# numpad.net
KiCad netlist of a schematic drawn in EAGLE
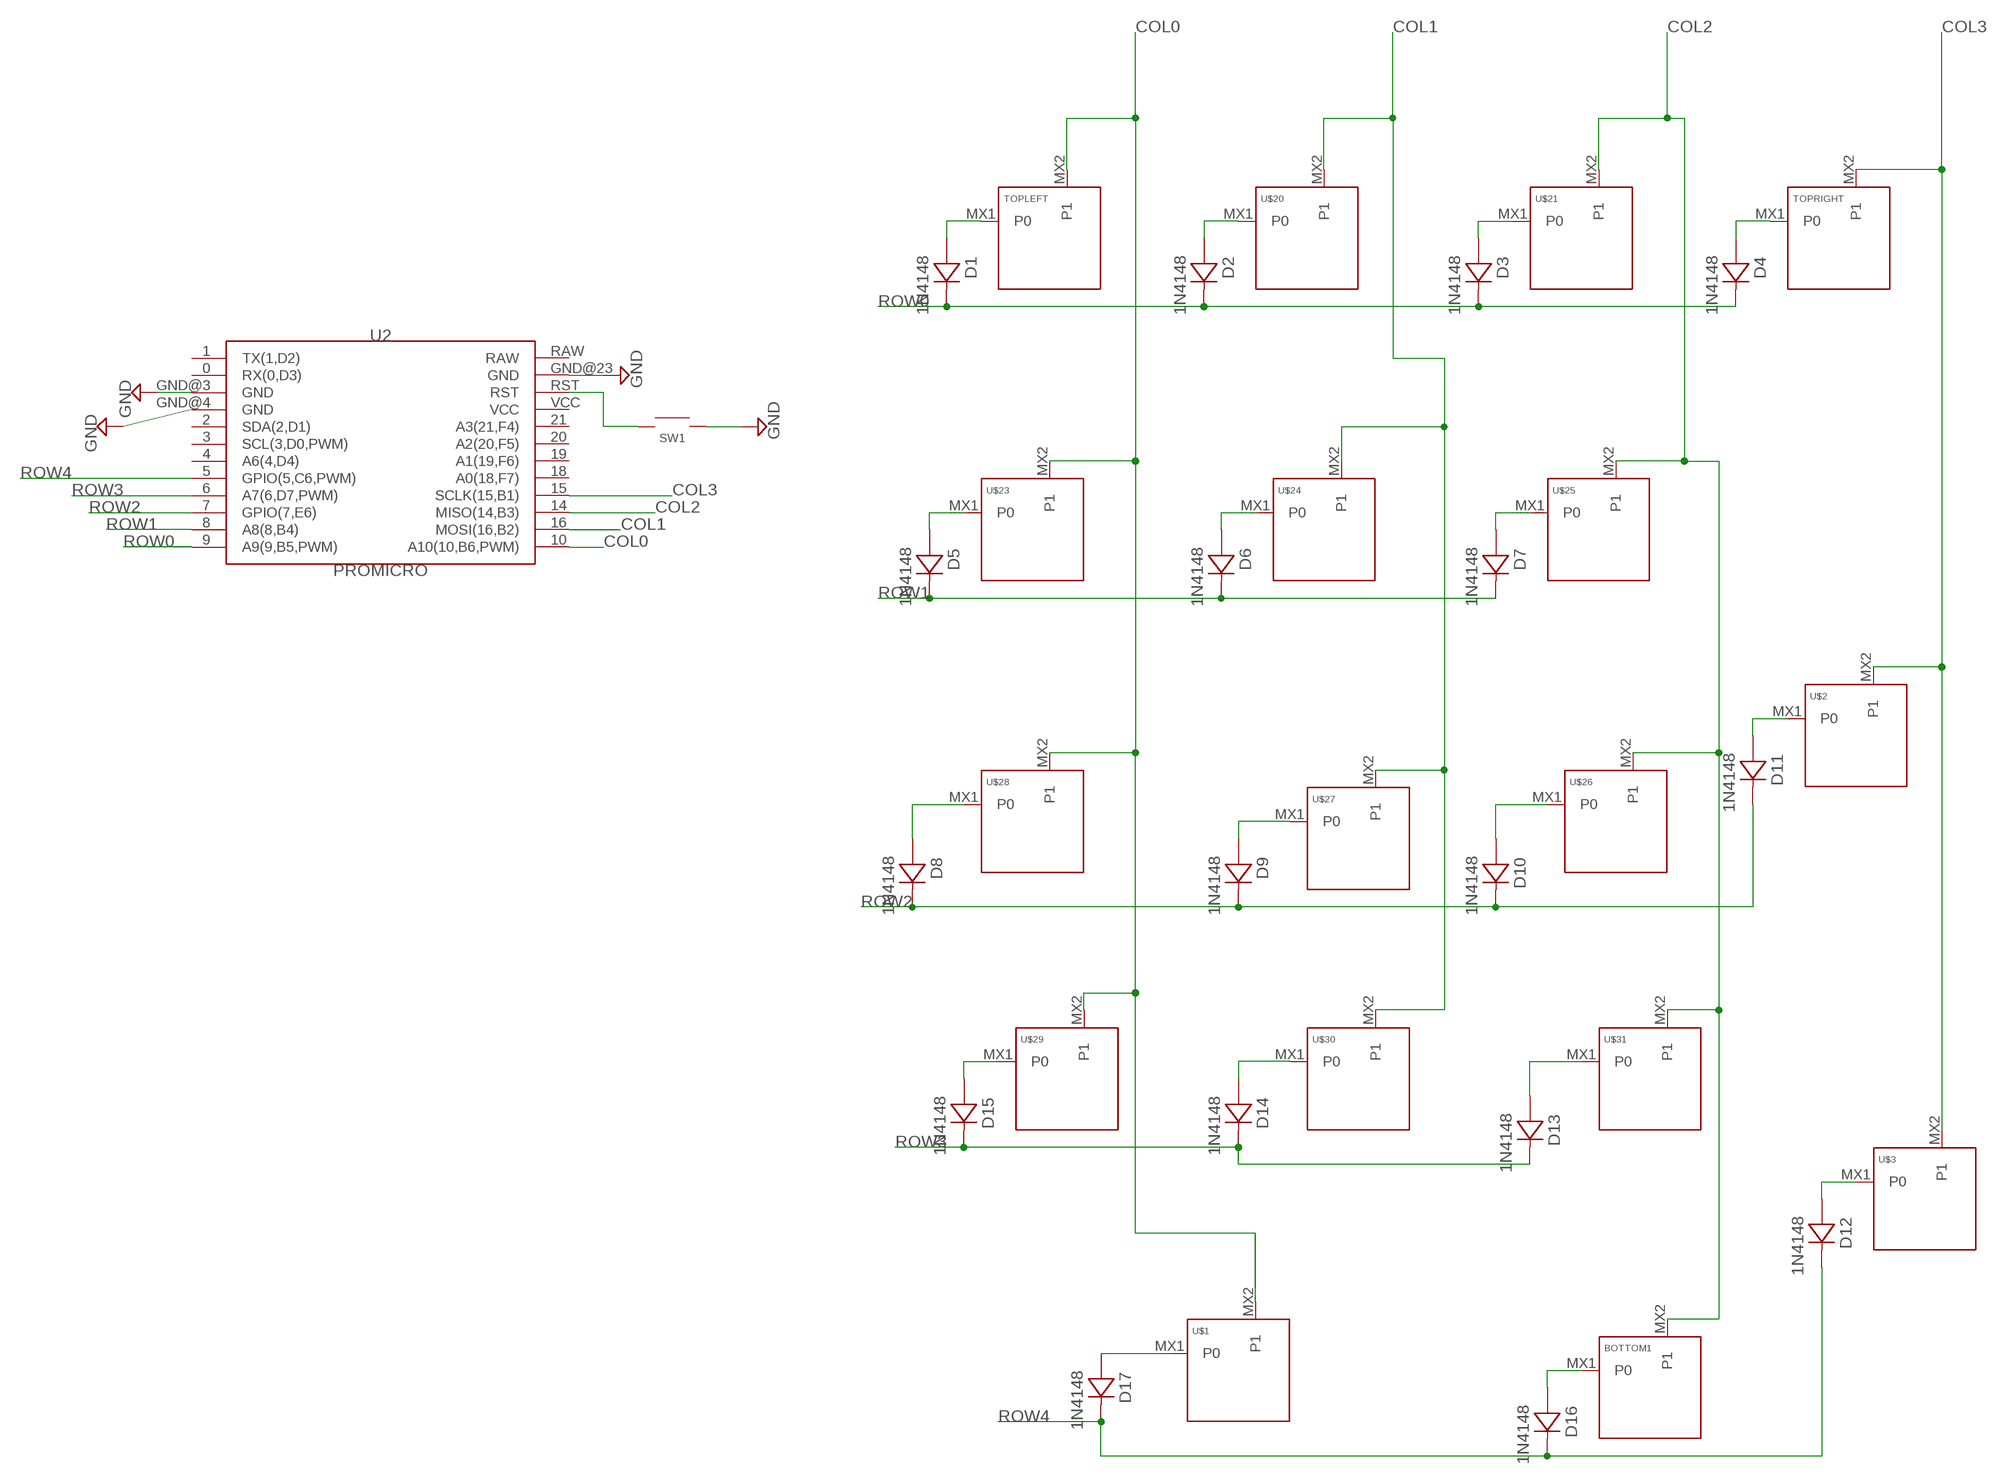
[diagram p0: schematic, sheet 1]

(export (version "E")
  (design (tool "Eeschema 10.0.6"))
  (components
    (comp (ref "BOTTOM1")
      (value "KEYSWITCH-PLAIN-MX-1U")
      (footprint "eagle-import:MX-1U")
      (libsource (lib "eagle-import") (part "KEYSWITCH-PLAIN-MX-1U"))
    )
    (comp (ref "D1")
      (value "1N4148")
      (footprint "eagle-import:DO-35")
      (libsource (lib "eagle-import") (part "DIODE-DO-35"))
    )
    (comp (ref "D2")
      (value "1N4148")
      (footprint "eagle-import:DO-35")
      (libsource (lib "eagle-import") (part "DIODE-DO-35"))
    )
    (comp (ref "D3")
      (value "1N4148")
      (footprint "eagle-import:DO-35")
      (libsource (lib "eagle-import") (part "DIODE-DO-35"))
    )
    (comp (ref "D4")
      (value "1N4148")
      (footprint "eagle-import:DO-35")
      (libsource (lib "eagle-import") (part "DIODE-DO-35"))
    )
    (comp (ref "D5")
      (value "1N4148")
      (footprint "eagle-import:DO-35")
      (libsource (lib "eagle-import") (part "DIODE-DO-35"))
    )
    (comp (ref "D6")
      (value "1N4148")
      (footprint "eagle-import:DO-35")
      (libsource (lib "eagle-import") (part "DIODE-DO-35"))
    )
    (comp (ref "D7")
      (value "1N4148")
      (footprint "eagle-import:DO-35")
      (libsource (lib "eagle-import") (part "DIODE-DO-35"))
    )
    (comp (ref "D8")
      (value "1N4148")
      (footprint "eagle-import:DO-35")
      (libsource (lib "eagle-import") (part "DIODE-DO-35"))
    )
    (comp (ref "D9")
      (value "1N4148")
      (footprint "eagle-import:DO-35")
      (libsource (lib "eagle-import") (part "DIODE-DO-35"))
    )
    (comp (ref "D10")
      (value "1N4148")
      (footprint "eagle-import:DO-35")
      (libsource (lib "eagle-import") (part "DIODE-DO-35"))
    )
    (comp (ref "D11")
      (value "1N4148")
      (footprint "eagle-import:DO-35")
      (libsource (lib "eagle-import") (part "DIODE-DO-35"))
    )
    (comp (ref "D12")
      (value "1N4148")
      (footprint "eagle-import:DO-35")
      (libsource (lib "eagle-import") (part "DIODE-DO-35"))
    )
    (comp (ref "D13")
      (value "1N4148")
      (footprint "eagle-import:DO-35")
      (libsource (lib "eagle-import") (part "DIODE-DO-35"))
    )
    (comp (ref "D14")
      (value "1N4148")
      (footprint "eagle-import:DO-35")
      (libsource (lib "eagle-import") (part "DIODE-DO-35"))
    )
    (comp (ref "D15")
      (value "1N4148")
      (footprint "eagle-import:DO-35")
      (libsource (lib "eagle-import") (part "DIODE-DO-35"))
    )
    (comp (ref "D16")
      (value "1N4148")
      (footprint "eagle-import:DO-35")
      (libsource (lib "eagle-import") (part "DIODE-DO-35"))
    )
    (comp (ref "D17")
      (value "1N4148")
      (footprint "eagle-import:DO-35")
      (libsource (lib "eagle-import") (part "DIODE-DO-35"))
    )
    (comp (ref "SW1")
      (value "SWITCH-SMD-SCHURTER-1241.1612.11")
      (footprint "eagle-import:SWITCH-SMD-SCHURTER-1241.1612.11")
      (libsource (lib "eagle-import") (part "SWITCH-SMD-SCHURTER-1241.1612.11"))
    )
    (comp (ref "TOPLEFT")
      (value "KEYSWITCH-PLAIN-MX-1U")
      (footprint "eagle-import:MX-1U")
      (libsource (lib "eagle-import") (part "KEYSWITCH-PLAIN-MX-1U"))
    )
    (comp (ref "TOPRIGHT")
      (value "KEYSWITCH-PLAIN-MX-1U")
      (footprint "eagle-import:MX-1U")
      (libsource (lib "eagle-import") (part "KEYSWITCH-PLAIN-MX-1U"))
    )
    (comp (ref "U$1")
      (value "KEYSWITCH-PLAIN-MX-2U-FLIPPED")
      (footprint "eagle-import:MX-2U-FLIPPED")
      (libsource (lib "eagle-import") (part "KEYSWITCH-PLAIN-MX-2U-FLIPPED"))
    )
    (comp (ref "U$2")
      (value "KEYSWITCH-PLAIN-MX-2U-ROTATED")
      (footprint "eagle-import:MX-2U-ROTATED")
      (libsource (lib "eagle-import") (part "KEYSWITCH-PLAIN-MX-2U-ROTATED"))
    )
    (comp (ref "U$3")
      (value "KEYSWITCH-PLAIN-MX-2U-ROTATED")
      (footprint "eagle-import:MX-2U-ROTATED")
      (libsource (lib "eagle-import") (part "KEYSWITCH-PLAIN-MX-2U-ROTATED"))
    )
    (comp (ref "U$20")
      (value "KEYSWITCH-PLAIN-MX-1U")
      (footprint "eagle-import:MX-1U")
      (libsource (lib "eagle-import") (part "KEYSWITCH-PLAIN-MX-1U"))
    )
    (comp (ref "U$21")
      (value "KEYSWITCH-PLAIN-MX-1U")
      (footprint "eagle-import:MX-1U")
      (libsource (lib "eagle-import") (part "KEYSWITCH-PLAIN-MX-1U"))
    )
    (comp (ref "U$23")
      (value "KEYSWITCH-PLAIN-MX-1U")
      (footprint "eagle-import:MX-1U")
      (libsource (lib "eagle-import") (part "KEYSWITCH-PLAIN-MX-1U"))
    )
    (comp (ref "U$24")
      (value "KEYSWITCH-PLAIN-MX-1U")
      (footprint "eagle-import:MX-1U")
      (libsource (lib "eagle-import") (part "KEYSWITCH-PLAIN-MX-1U"))
    )
    (comp (ref "U$25")
      (value "KEYSWITCH-PLAIN-MX-1U")
      (footprint "eagle-import:MX-1U")
      (libsource (lib "eagle-import") (part "KEYSWITCH-PLAIN-MX-1U"))
    )
    (comp (ref "U$26")
      (value "KEYSWITCH-PLAIN-MX-1U")
      (footprint "eagle-import:MX-1U")
      (libsource (lib "eagle-import") (part "KEYSWITCH-PLAIN-MX-1U"))
    )
    (comp (ref "U$27")
      (value "KEYSWITCH-PLAIN-MX-1U")
      (footprint "eagle-import:MX-1U")
      (libsource (lib "eagle-import") (part "KEYSWITCH-PLAIN-MX-1U"))
    )
    (comp (ref "U$28")
      (value "KEYSWITCH-PLAIN-MX-1U")
      (footprint "eagle-import:MX-1U")
      (libsource (lib "eagle-import") (part "KEYSWITCH-PLAIN-MX-1U"))
    )
    (comp (ref "U$29")
      (value "KEYSWITCH-PLAIN-MX-1U")
      (footprint "eagle-import:MX-1U")
      (libsource (lib "eagle-import") (part "KEYSWITCH-PLAIN-MX-1U"))
    )
    (comp (ref "U$30")
      (value "KEYSWITCH-PLAIN-MX-1U")
      (footprint "eagle-import:MX-1U")
      (libsource (lib "eagle-import") (part "KEYSWITCH-PLAIN-MX-1U"))
    )
    (comp (ref "U$31")
      (value "KEYSWITCH-PLAIN-MX-1U")
      (footprint "eagle-import:MX-1U")
      (libsource (lib "eagle-import") (part "KEYSWITCH-PLAIN-MX-1U"))
    )
    (comp (ref "U2")
      (value "PROMICRO")
      (footprint "eagle-import:PROMICRO")
      (libsource (lib "eagle-import") (part "PROMICRO"))
    )
  )
  (nets
    (net (code "1") (name "/COL0") (class "Default")
      (node (ref "TOPLEFT") (pin "MX2") (pinfunction "P1_MX2") (pintype "bidirectional"))
      (node (ref "U$1") (pin "MX2") (pinfunction "P1_MX2") (pintype "bidirectional"))
      (node (ref "U$23") (pin "MX2") (pinfunction "P1_MX2") (pintype "bidirectional"))
      (node (ref "U$28") (pin "MX2") (pinfunction "P1_MX2") (pintype "bidirectional"))
      (node (ref "U$29") (pin "MX2") (pinfunction "P1_MX2") (pintype "bidirectional"))
      (node (ref "U2") (pin "10") (pinfunction "A10(10,B6,PWM)_10") (pintype "bidirectional"))
    )
    (net (code "2") (name "/COL1") (class "Default")
      (node (ref "U$20") (pin "MX2") (pinfunction "P1_MX2") (pintype "bidirectional"))
      (node (ref "U$24") (pin "MX2") (pinfunction "P1_MX2") (pintype "bidirectional"))
      (node (ref "U$27") (pin "MX2") (pinfunction "P1_MX2") (pintype "bidirectional"))
      (node (ref "U$30") (pin "MX2") (pinfunction "P1_MX2") (pintype "bidirectional"))
      (node (ref "U2") (pin "16") (pinfunction "MOSI(16,B2)_16") (pintype "bidirectional"))
    )
    (net (code "3") (name "/COL2") (class "Default")
      (node (ref "BOTTOM1") (pin "MX2") (pinfunction "P1_MX2") (pintype "bidirectional"))
      (node (ref "U$21") (pin "MX2") (pinfunction "P1_MX2") (pintype "bidirectional"))
      (node (ref "U$25") (pin "MX2") (pinfunction "P1_MX2") (pintype "bidirectional"))
      (node (ref "U$26") (pin "MX2") (pinfunction "P1_MX2") (pintype "bidirectional"))
      (node (ref "U$31") (pin "MX2") (pinfunction "P1_MX2") (pintype "bidirectional"))
      (node (ref "U2") (pin "14") (pinfunction "MISO(14,B3)_14") (pintype "bidirectional"))
    )
    (net (code "4") (name "/COL3") (class "Default")
      (node (ref "TOPRIGHT") (pin "MX2") (pinfunction "P1_MX2") (pintype "bidirectional"))
      (node (ref "U$2") (pin "MX2") (pinfunction "P1_MX2") (pintype "bidirectional"))
      (node (ref "U$3") (pin "MX2") (pinfunction "P1_MX2") (pintype "bidirectional"))
      (node (ref "U2") (pin "15") (pinfunction "SCLK(15,B1)_15") (pintype "bidirectional"))
    )
    (net (code "5") (name "/ROW0") (class "Default")
      (node (ref "D1") (pin "C") (pinfunction "C_C") (pintype "passive"))
      (node (ref "D2") (pin "C") (pinfunction "C_C") (pintype "passive"))
      (node (ref "D3") (pin "C") (pinfunction "C_C") (pintype "passive"))
      (node (ref "D4") (pin "C") (pinfunction "C_C") (pintype "passive"))
      (node (ref "U2") (pin "9") (pinfunction "A9(9,B5,PWM)_9") (pintype "bidirectional"))
    )
    (net (code "6") (name "/ROW1") (class "Default")
      (node (ref "D5") (pin "C") (pinfunction "C_C") (pintype "passive"))
      (node (ref "D6") (pin "C") (pinfunction "C_C") (pintype "passive"))
      (node (ref "D7") (pin "C") (pinfunction "C_C") (pintype "passive"))
      (node (ref "U2") (pin "8") (pinfunction "A8(8,B4)_8") (pintype "bidirectional"))
    )
    (net (code "7") (name "/ROW2") (class "Default")
      (node (ref "D10") (pin "C") (pinfunction "C_C") (pintype "passive"))
      (node (ref "D11") (pin "C") (pinfunction "C_C") (pintype "passive"))
      (node (ref "D8") (pin "C") (pinfunction "C_C") (pintype "passive"))
      (node (ref "D9") (pin "C") (pinfunction "C_C") (pintype "passive"))
      (node (ref "U2") (pin "7") (pinfunction "GPIO(7,E6)_7") (pintype "bidirectional"))
    )
    (net (code "8") (name "/ROW3") (class "Default")
      (node (ref "D13") (pin "C") (pinfunction "C_C") (pintype "passive"))
      (node (ref "D14") (pin "C") (pinfunction "C_C") (pintype "passive"))
      (node (ref "D15") (pin "C") (pinfunction "C_C") (pintype "passive"))
      (node (ref "U2") (pin "6") (pinfunction "A7(6,D7,PWM)_6") (pintype "bidirectional"))
    )
    (net (code "9") (name "/ROW4") (class "Default")
      (node (ref "D12") (pin "C") (pinfunction "C_C") (pintype "passive"))
      (node (ref "D16") (pin "C") (pinfunction "C_C") (pintype "passive"))
      (node (ref "D17") (pin "C") (pinfunction "C_C") (pintype "passive"))
      (node (ref "U2") (pin "5") (pinfunction "GPIO(5,C6,PWM)_5") (pintype "bidirectional"))
    )
    (net (code "10") (name "GND") (class "Default")
      (node (ref "SW1") (pin "2A") (pinfunction "2_2A") (pintype "passive"))
      (node (ref "SW1") (pin "2B") (pinfunction "2_2B") (pintype "passive"))
      (node (ref "U2") (pin "GND@23") (pinfunction "GND_GND@23") (pintype "bidirectional"))
      (node (ref "U2") (pin "GND@3") (pinfunction "GND_GND@3") (pintype "bidirectional"))
      (node (ref "U2") (pin "GND@4") (pinfunction "GND_GND@4") (pintype "bidirectional"))
    )
    (net (code "11") (name "Net-(BOTTOM1-P0)") (class "Default")
      (node (ref "BOTTOM1") (pin "MX1") (pinfunction "P0_MX1") (pintype "bidirectional"))
      (node (ref "D16") (pin "A") (pinfunction "A_A") (pintype "passive"))
    )
    (net (code "12") (name "Net-(SW1-1-Pad1A)") (class "Default")
      (node (ref "SW1") (pin "1A") (pinfunction "1_1A") (pintype "passive"))
      (node (ref "SW1") (pin "1B") (pinfunction "1_1B") (pintype "passive"))
      (node (ref "U2") (pin "RST") (pinfunction "RST_RST") (pintype "bidirectional"))
    )
    (net (code "13") (name "Net-(TOPLEFT-P0)") (class "Default")
      (node (ref "D1") (pin "A") (pinfunction "A_A") (pintype "passive"))
      (node (ref "TOPLEFT") (pin "MX1") (pinfunction "P0_MX1") (pintype "bidirectional"))
    )
    (net (code "14") (name "Net-(TOPRIGHT-P0)") (class "Default")
      (node (ref "D4") (pin "A") (pinfunction "A_A") (pintype "passive"))
      (node (ref "TOPRIGHT") (pin "MX1") (pinfunction "P0_MX1") (pintype "bidirectional"))
    )
    (net (code "15") (name "Net-(U$1-P0)") (class "Default")
      (node (ref "D17") (pin "A") (pinfunction "A_A") (pintype "passive"))
      (node (ref "U$1") (pin "MX1") (pinfunction "P0_MX1") (pintype "bidirectional"))
    )
    (net (code "16") (name "Net-(U$2-P0)") (class "Default")
      (node (ref "D11") (pin "A") (pinfunction "A_A") (pintype "passive"))
      (node (ref "U$2") (pin "MX1") (pinfunction "P0_MX1") (pintype "bidirectional"))
    )
    (net (code "17") (name "Net-(U$3-P0)") (class "Default")
      (node (ref "D12") (pin "A") (pinfunction "A_A") (pintype "passive"))
      (node (ref "U$3") (pin "MX1") (pinfunction "P0_MX1") (pintype "bidirectional"))
    )
    (net (code "18") (name "Net-(U$20-P0)") (class "Default")
      (node (ref "D2") (pin "A") (pinfunction "A_A") (pintype "passive"))
      (node (ref "U$20") (pin "MX1") (pinfunction "P0_MX1") (pintype "bidirectional"))
    )
    (net (code "19") (name "Net-(U$21-P0)") (class "Default")
      (node (ref "D3") (pin "A") (pinfunction "A_A") (pintype "passive"))
      (node (ref "U$21") (pin "MX1") (pinfunction "P0_MX1") (pintype "bidirectional"))
    )
    (net (code "20") (name "Net-(U$23-P0)") (class "Default")
      (node (ref "D5") (pin "A") (pinfunction "A_A") (pintype "passive"))
      (node (ref "U$23") (pin "MX1") (pinfunction "P0_MX1") (pintype "bidirectional"))
    )
    (net (code "21") (name "Net-(U$24-P0)") (class "Default")
      (node (ref "D6") (pin "A") (pinfunction "A_A") (pintype "passive"))
      (node (ref "U$24") (pin "MX1") (pinfunction "P0_MX1") (pintype "bidirectional"))
    )
    (net (code "22") (name "Net-(U$25-P0)") (class "Default")
      (node (ref "D7") (pin "A") (pinfunction "A_A") (pintype "passive"))
      (node (ref "U$25") (pin "MX1") (pinfunction "P0_MX1") (pintype "bidirectional"))
    )
    (net (code "23") (name "Net-(U$26-P0)") (class "Default")
      (node (ref "D10") (pin "A") (pinfunction "A_A") (pintype "passive"))
      (node (ref "U$26") (pin "MX1") (pinfunction "P0_MX1") (pintype "bidirectional"))
    )
    (net (code "24") (name "Net-(U$27-P0)") (class "Default")
      (node (ref "D9") (pin "A") (pinfunction "A_A") (pintype "passive"))
      (node (ref "U$27") (pin "MX1") (pinfunction "P0_MX1") (pintype "bidirectional"))
    )
    (net (code "25") (name "Net-(U$28-P0)") (class "Default")
      (node (ref "D8") (pin "A") (pinfunction "A_A") (pintype "passive"))
      (node (ref "U$28") (pin "MX1") (pinfunction "P0_MX1") (pintype "bidirectional"))
    )
    (net (code "26") (name "Net-(U$29-P0)") (class "Default")
      (node (ref "D15") (pin "A") (pinfunction "A_A") (pintype "passive"))
      (node (ref "U$29") (pin "MX1") (pinfunction "P0_MX1") (pintype "bidirectional"))
    )
    (net (code "27") (name "Net-(U$30-P0)") (class "Default")
      (node (ref "D14") (pin "A") (pinfunction "A_A") (pintype "passive"))
      (node (ref "U$30") (pin "MX1") (pinfunction "P0_MX1") (pintype "bidirectional"))
    )
    (net (code "28") (name "Net-(U$31-P0)") (class "Default")
      (node (ref "D13") (pin "A") (pinfunction "A_A") (pintype "passive"))
      (node (ref "U$31") (pin "MX1") (pinfunction "P0_MX1") (pintype "bidirectional"))
    )
    (net (code "29") (name "unconnected-(U2-A0(18,F7)-Pad18)") (class "Default")
      (node (ref "U2") (pin "18") (pinfunction "A0(18,F7)_18") (pintype "bidirectional"))
    )
    (net (code "30") (name "unconnected-(U2-A1(19,F6)-Pad19)") (class "Default")
      (node (ref "U2") (pin "19") (pinfunction "A1(19,F6)_19") (pintype "bidirectional"))
    )
    (net (code "31") (name "unconnected-(U2-A2(20,F5)-Pad20)") (class "Default")
      (node (ref "U2") (pin "20") (pinfunction "A2(20,F5)_20") (pintype "bidirectional"))
    )
    (net (code "32") (name "unconnected-(U2-A3(21,F4)-Pad21)") (class "Default")
      (node (ref "U2") (pin "21") (pinfunction "A3(21,F4)_21") (pintype "bidirectional"))
    )
    (net (code "33") (name "unconnected-(U2-A6(4,D4)-Pad4)") (class "Default")
      (node (ref "U2") (pin "4") (pinfunction "A6(4,D4)_4") (pintype "bidirectional"))
    )
    (net (code "34") (name "unconnected-(U2-PadRAW)") (class "Default")
      (node (ref "U2") (pin "RAW") (pinfunction "RAW_RAW") (pintype "bidirectional"))
    )
    (net (code "35") (name "unconnected-(U2-PadVCC)") (class "Default")
      (node (ref "U2") (pin "VCC") (pinfunction "VCC_VCC") (pintype "bidirectional"))
    )
    (net (code "36") (name "unconnected-(U2-RX(0,D3)-Pad0)") (class "Default")
      (node (ref "U2") (pin "0") (pinfunction "RX(0,D3)_0") (pintype "bidirectional"))
    )
    (net (code "37") (name "unconnected-(U2-SCL(3,D0,PWM)-Pad3)") (class "Default")
      (node (ref "U2") (pin "3") (pinfunction "SCL(3,D0,PWM)_3") (pintype "bidirectional"))
    )
    (net (code "38") (name "unconnected-(U2-SDA(2,D1)-Pad2)") (class "Default")
      (node (ref "U2") (pin "2") (pinfunction "SDA(2,D1)_2") (pintype "bidirectional"))
    )
    (net (code "39") (name "unconnected-(U2-TX(1,D2)-Pad1)") (class "Default")
      (node (ref "U2") (pin "1") (pinfunction "TX(1,D2)_1") (pintype "bidirectional"))
    )
  )
)
